# tracker_main.net
KiCad netlist of a schematic drawn in Altium Designer
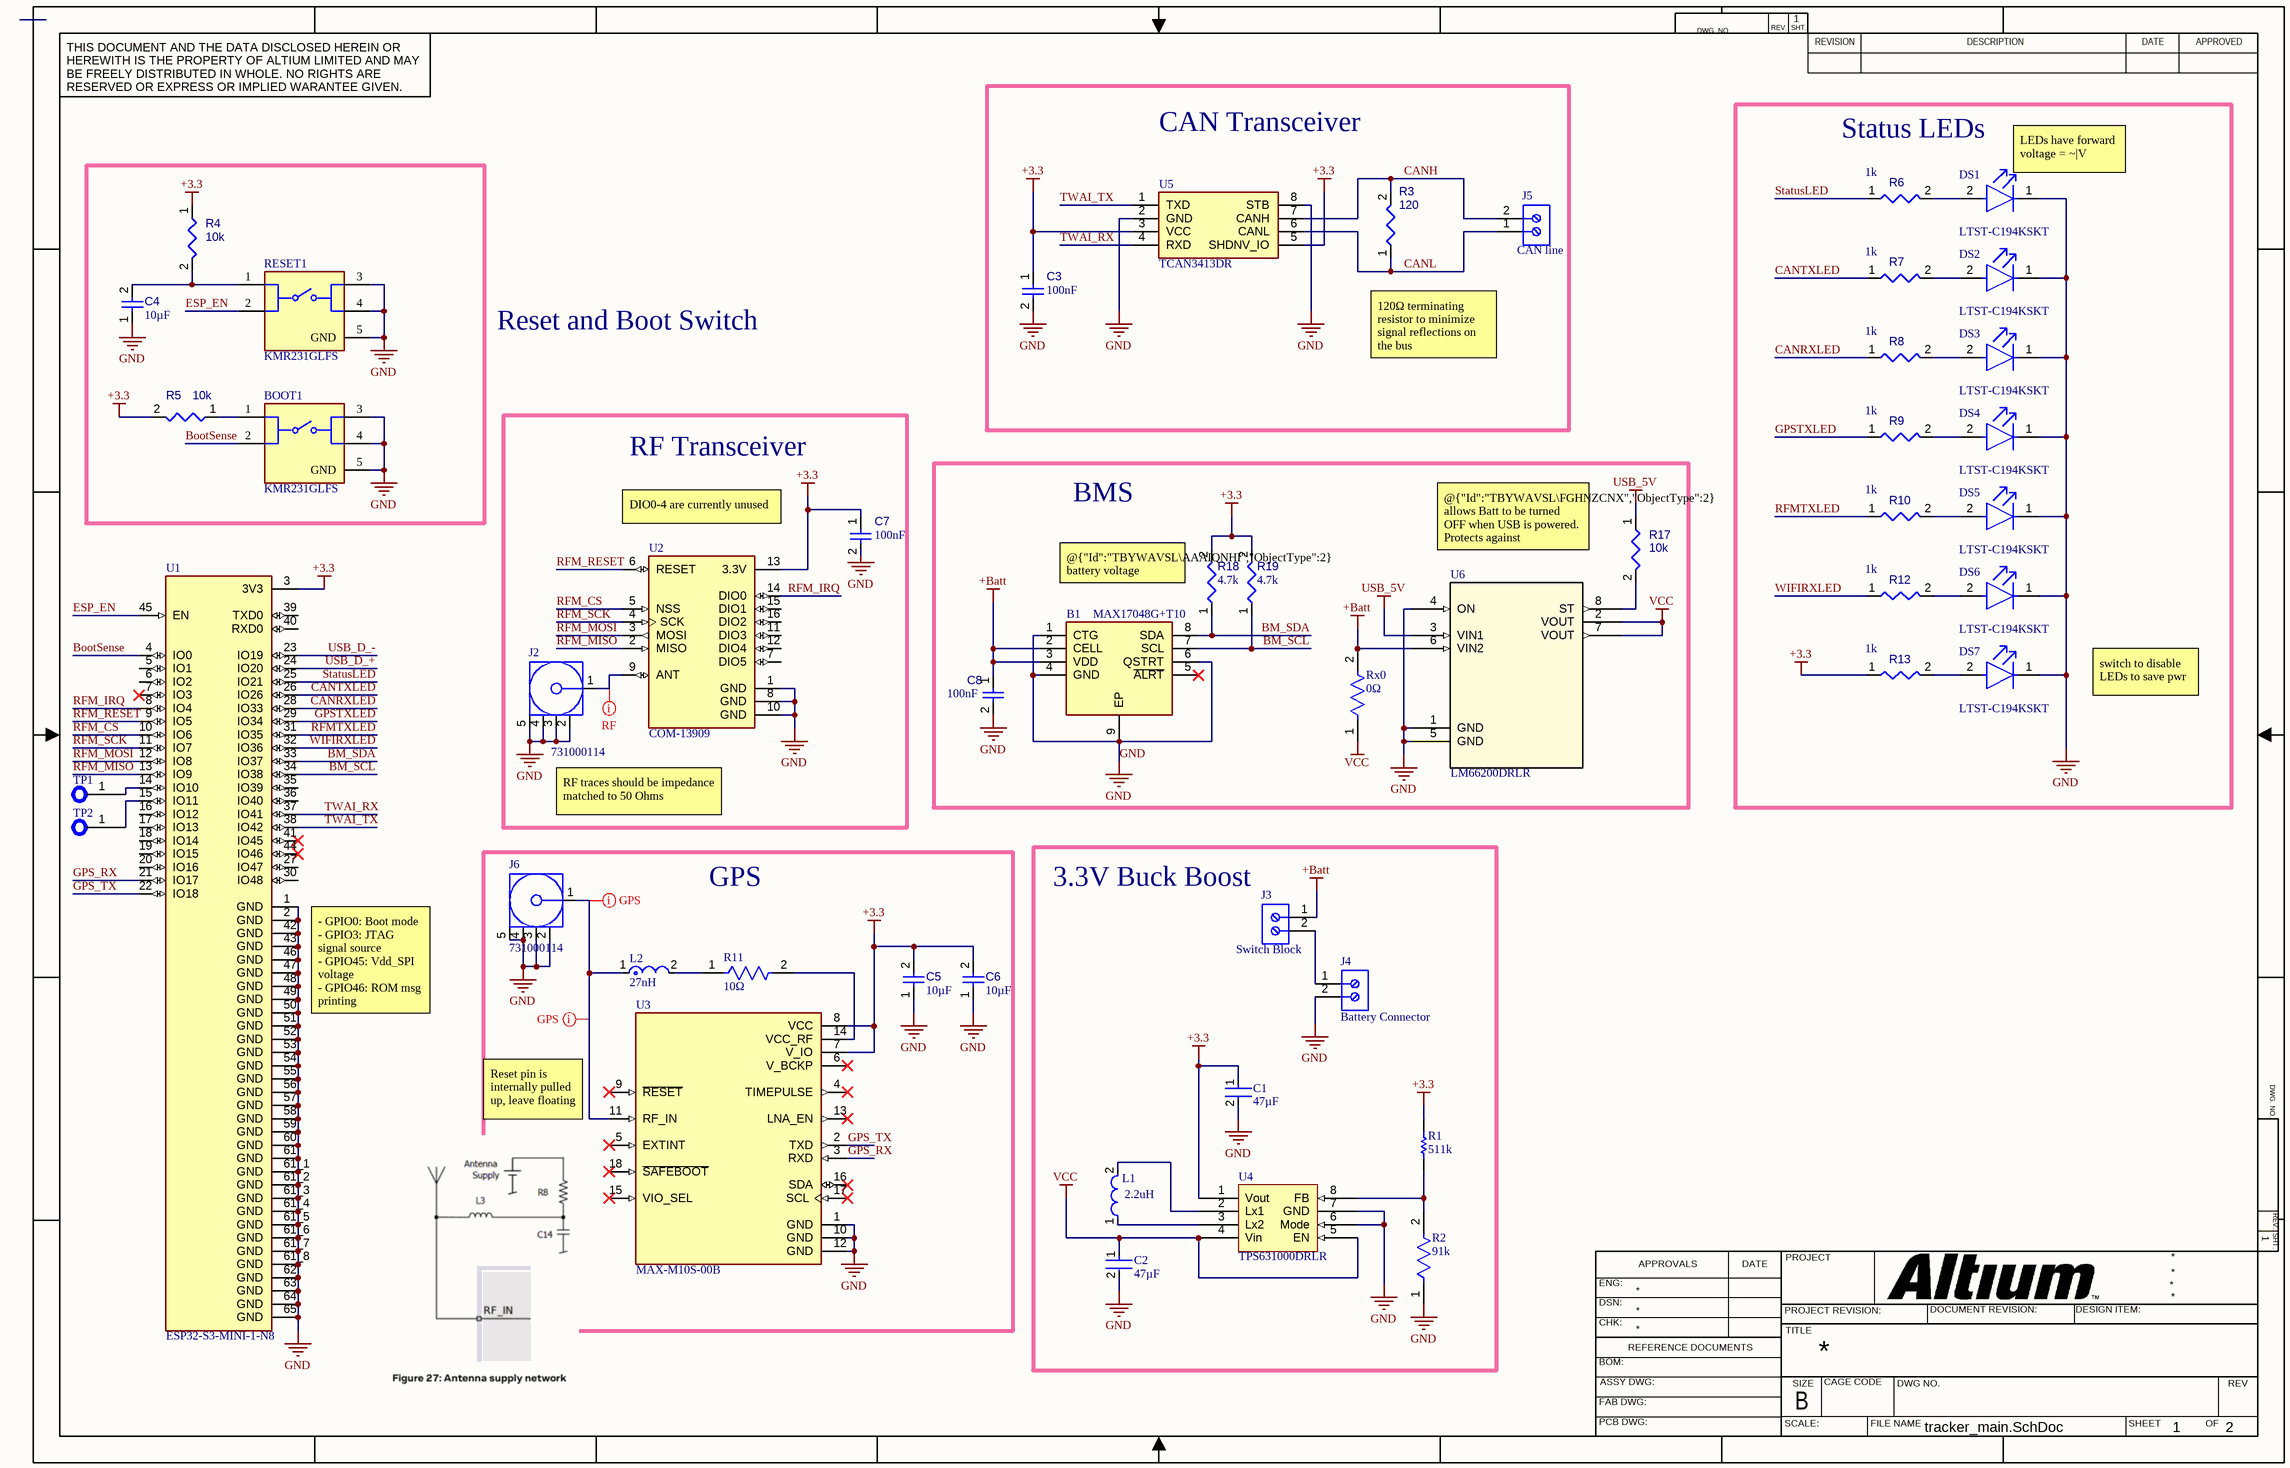
[diagram p0: tracker_main.SchDoc]

(export (version "E")
  (design (tool "Eeschema 10.0.6"))
  (components
    (comp (ref "B1")
      (value "MAX17048G+T10")
      (footprint "SON50P200X200X80-9N-D")
      (description "3A 1-Cell/2-Cell Fuel Gauge with ModelGauge")
      (fields (field (name "MOUSER PART NUMBER") "700-MAX17048G+T10"))
      (libsource (lib "UTD Workspace") (part "MAX17048G+T10"))
    )
    (comp (ref "BOOT1")
      (value "KMR231GLFS")
      (footprint "FP-KMR231GLFS-MFG")
      (description "SWITCH TACTILE SPST-NO 0.05A 32V")
      (libsource (lib "Altium Content Vault") (part "4ba73034ab40b7b0ce053ff7ec1e5b4"))
    )
    (comp (ref "C1")
      (value "47µF")
      (footprint "FP-0603-L_1_6_0_2-W_0_8_0-MFG")
      (description "CAP CER 47UF 6.3V X5R 0603\r\n06036D476MAT2A")
      (fields (field (name "TOLERANCE") "20%"))
      (libsource (lib "Altium Content Vault") (part "02cd4be3c70576c341d710602a673aa"))
    )
    (comp (ref "C2")
      (value "47µF")
      (footprint "FP-0603-L_1_6_0_2-W_0_8_0-MFG")
      (description "CAP CER 47UF 6.3V X5R 0603\r\n06036D476MAT2A")
      (fields (field (name "TOLERANCE") "20%"))
      (libsource (lib "Altium Content Vault") (part "02cd4be3c70576c341d710602a673aa"))
    )
    (comp (ref "C3")
      (value "100nF")
      (footprint "CAPC1608X90X40NL10T20")
      (description "Chip Capacitor, 100 nF, +/- 10%, 50 V, 0603 (1608 Metric)")
      (fields (field (name "TOLERANCE") "10%"))
      (libsource (lib "Aadesh Senthilkumar") (part "CAP-NP-2"))
    )
    (comp (ref "C4")
      (value "10µF")
      (footprint "CAPC0603(1608)100_L")
      (description "Chip Capacitor, 10µF +/-20%, 10V, 0603, Thickness 1 mm")
      (fields (field (name "TOLERANCE") "10%") (field (name "Comment") "Capacitor 10µF +/-20% 10V 0603"))
      (libsource (lib "The University of Texas at Dallas") (part "CAP-NP-2"))
    )
    (comp (ref "C5")
      (value "10µF")
      (footprint "CAPC0603(1608)100_L")
      (description "Chip Capacitor, 10µF +/-20%, 10V, 0603, Thickness 1 mm")
      (fields (field (name "TOLERANCE") "10%") (field (name "Comment") "Capacitor 10µF +/-20% 10V 0603"))
      (libsource (lib "The University of Texas at Dallas") (part "CAP-NP-2"))
    )
    (comp (ref "C6")
      (value "10µF")
      (footprint "CAPC0603(1608)100_L")
      (description "Chip Capacitor, 10µF +/-20%, 10V, 0603, Thickness 1 mm")
      (fields (field (name "TOLERANCE") "10%") (field (name "Comment") "Capacitor 10µF +/-20% 10V 0603"))
      (libsource (lib "The University of Texas at Dallas") (part "CAP-NP-2"))
    )
    (comp (ref "C7")
      (value "100nF")
      (footprint "CAPC1608X90X40NL10T20")
      (description "Chip Capacitor, 100 nF, +/- 10%, 50 V, 0603 (1608 Metric)")
      (fields (field (name "TOLERANCE") "10%"))
      (libsource (lib "Aadesh Senthilkumar") (part "CAP-NP-2"))
    )
    (comp (ref "C8")
      (value "100nF")
      (footprint "CAPC1608X90X40NL10T20")
      (description "Chip Capacitor, 100 nF, +/- 10%, 50 V, 0603 (1608 Metric)")
      (fields (field (name "TOLERANCE") "10%"))
      (libsource (lib "Aadesh Senthilkumar") (part "CAP-NP-2"))
    )
    (comp (ref "DS1")
      (value "LTST-C194KSKT")
      (footprint "FP-LTST-C194KSKT-MFG")
      (description "Single Color LED, Yellow, Water Clear, 1.15mm")
      (libsource (lib "UTD Workspace") (part "8706943c75ba83719d021d2fdc84c58"))
    )
    (comp (ref "DS2")
      (value "LTST-C194KSKT")
      (footprint "FP-LTST-C194KSKT-MFG")
      (description "Single Color LED, Yellow, Water Clear, 1.15mm")
      (libsource (lib "UTD Workspace") (part "8706943c75ba83719d021d2fdc84c58"))
    )
    (comp (ref "DS3")
      (value "LTST-C194KSKT")
      (footprint "FP-LTST-C194KSKT-MFG")
      (description "Single Color LED, Yellow, Water Clear, 1.15mm")
      (libsource (lib "UTD Workspace") (part "8706943c75ba83719d021d2fdc84c58"))
    )
    (comp (ref "DS4")
      (value "LTST-C194KSKT")
      (footprint "FP-LTST-C194KSKT-MFG")
      (description "Single Color LED, Yellow, Water Clear, 1.15mm")
      (libsource (lib "UTD Workspace") (part "8706943c75ba83719d021d2fdc84c58"))
    )
    (comp (ref "DS5")
      (value "LTST-C194KSKT")
      (footprint "FP-LTST-C194KSKT-MFG")
      (description "Single Color LED, Yellow, Water Clear, 1.15mm")
      (libsource (lib "UTD Workspace") (part "8706943c75ba83719d021d2fdc84c58"))
    )
    (comp (ref "DS6")
      (value "LTST-C194KSKT")
      (footprint "FP-LTST-C194KSKT-MFG")
      (description "Single Color LED, Yellow, Water Clear, 1.15mm")
      (libsource (lib "UTD Workspace") (part "8706943c75ba83719d021d2fdc84c58"))
    )
    (comp (ref "DS7")
      (value "LTST-C194KSKT")
      (footprint "FP-LTST-C194KSKT-MFG")
      (description "Single Color LED, Yellow, Water Clear, 1.15mm")
      (libsource (lib "UTD Workspace") (part "8706943c75ba83719d021d2fdc84c58"))
    )
    (comp (ref "J2")
      (value "731000114")
      (footprint "MOLX-731000114_V")
      (description "SMA Right-Angle PCB Jack Receptacle, Brass Body, Gold Plated, 50 Ohm, 5-Pin THD, RoHS, Tray")
      (fields (field (name "MANUFACTURER") "Molex"))
      (libsource (lib "Altium Content Vault") (part "CN-S-4F-RF5"))
    )
    (comp (ref "J3")
      (value "Switch Block")
      (footprint "PHOE-1725656-2")
      (description "Male Header, Pitch 2.54 mm, 1 x 2 Position, Height 9 mm, Tail Length 3.5 mm")
      (fields
        (field (name "MANUFACTURER PART NO.") "1725656")
        (field (name "MANUFACTURER") "Phoenix Contact")
      )
      (libsource (lib "Altium Content Vault") (part "CN-1P-F-TB2"))
    )
    (comp (ref "J4")
      (value "Battery Connector")
      (footprint "PHOE-1725656-2")
      (description "Male Header, Pitch 2.54 mm, 1 x 2 Position, Height 9 mm, Tail Length 3.5 mm")
      (fields
        (field (name "MANUFACTURER PART NO.") "1725656")
        (field (name "MANUFACTURER") "Phoenix Contact")
      )
      (libsource (lib "Altium Content Vault") (part "CN-1P-F-TB2"))
    )
    (comp (ref "J5")
      (value "CAN line")
      (footprint "PHOE-1725656-2")
      (description "Male Header, Pitch 2.54 mm, 1 x 2 Position, Height 9 mm, Tail Length 3.5 mm")
      (fields
        (field (name "MANUFACTURER PART NO.") "1725656")
        (field (name "MANUFACTURER") "Phoenix Contact")
      )
      (libsource (lib "Altium Content Vault") (part "CN-1P-F-TB2"))
    )
    (comp (ref "J6")
      (value "731000114")
      (footprint "MOLX-731000114_V")
      (description "SMA Right-Angle PCB Jack Receptacle, Brass Body, Gold Plated, 50 Ohm, 5-Pin THD, RoHS, Tray")
      (fields (field (name "MANUFACTURER") "Molex"))
      (libsource (lib "Altium Content Vault") (part "CN-S-4F-RF5"))
    )
    (comp (ref "L1")
      (value "2.2uH")
      (footprint "FP-DFE21CC_EL-MFG")
      (description "FIXED IND 2.2UH 2100MA NONAUTO")
      (fields (field (name "Comment") "DFE21CCN2R2MELL"))
      (libsource (lib "Altium Content Vault") (part "725321dda6339637d4d059423bc1c3c"))
    )
    (comp (ref "L2")
      (value "27nH")
      (footprint "FP-LQG18HH_00-IPC_C")
      (description "Multilayer type Inductor for Automotive 27nH ±5% 0.54Ω 500mA 0603 LQG18HH27NJ00D")
      (libsource (lib "Altium Content Vault") (part "4cc4b267dca4c8e51f7102f422741d8"))
    )
    (comp (ref "R1")
      (value "511k")
      (footprint "RESC1609X50X30NL10T20")
      (description "CRCW0603511KFKEA\r\nRes Thick Film 0603 511K Ohm 1% 0.1W(1/10W) ±100ppm/C Pad SMD Automotive T/R")
      (fields (field (name "PART NUMBER") "CRCW0603511KFKEA") (field (name "MANUFACTURER") "Vishay Dale"))
      (libsource (lib "Altium Content Vault") (part "RES"))
    )
    (comp (ref "R2")
      (value "91k")
      (footprint "FP-CRCW0603-HPe3-IPC_B")
      (description "CRCW060391K0FKEAHP\r\nRES Thick Film, 91kΩ, 1%, 0.33W, 100ppm/°C, 0603")
      (fields (field (name "TOLERANCE") "1%"))
      (libsource (lib "Altium Content Vault") (part "1029c3af85768c4190bb7ad29bc67b5"))
    )
    (comp (ref "R3")
      (value "120")
      (footprint "RESC0603(1608)_L")
      (description "Chip Resistor, 120 Ohms, +/-5 %, 0.1 W, -55 to 155 degC, 0603")
      (fields (field (name "TOLERANCE") "5%") (field (name "POWER") "100mW"))
      (libsource (lib "Aadesh Senthilkumar") (part "RES-2"))
    )
    (comp (ref "R4")
      (value "10k")
      (footprint "RESC1608X55X25ML10T15")
      (description "Chip Resistor, 10 KOhm, +/- 1%, 01 W, -55 to 155 degC, 0603 (1608 Metric)")
      (fields (field (name "POWER") "100mW") (field (name "TOLERANCE") "1%"))
      (libsource (lib "Aadesh Senthilkumar") (part "RES-2"))
    )
    (comp (ref "R5")
      (value "10k")
      (footprint "RESC1608X55X25ML10T15")
      (description "Chip Resistor, 10 KOhm, +/- 1%, 01 W, -55 to 155 degC, 0603 (1608 Metric)")
      (fields (field (name "POWER") "100mW") (field (name "TOLERANCE") "1%"))
      (libsource (lib "Aadesh Senthilkumar") (part "RES-2"))
    )
    (comp (ref "R6")
      (value "1k")
      (footprint "RESC1608X55X25ML10T15")
      (description "Chip Resistor, 1 KOhm, +/-1%, 0.1 W, -55 to 155 degC, 0603 (1608 Metric)")
      (fields (field (name "TOLERANCE") "1%") (field (name "POWER") "100mW"))
      (libsource (lib "UTD Workspace") (part "RES-2"))
    )
    (comp (ref "R7")
      (value "1k")
      (footprint "RESC1608X55X25ML10T15")
      (description "Chip Resistor, 1 KOhm, +/-1%, 0.1 W, -55 to 155 degC, 0603 (1608 Metric)")
      (fields (field (name "TOLERANCE") "1%") (field (name "POWER") "100mW"))
      (libsource (lib "UTD Workspace") (part "RES-2"))
    )
    (comp (ref "R8")
      (value "1k")
      (footprint "RESC1608X55X25ML10T15")
      (description "Chip Resistor, 1 KOhm, +/-1%, 0.1 W, -55 to 155 degC, 0603 (1608 Metric)")
      (fields (field (name "TOLERANCE") "1%") (field (name "POWER") "100mW"))
      (libsource (lib "UTD Workspace") (part "RES-2"))
    )
    (comp (ref "R9")
      (value "1k")
      (footprint "RESC1608X55X25ML10T15")
      (description "Chip Resistor, 1 KOhm, +/-1%, 0.1 W, -55 to 155 degC, 0603 (1608 Metric)")
      (fields (field (name "TOLERANCE") "1%") (field (name "POWER") "100mW"))
      (libsource (lib "UTD Workspace") (part "RES-2"))
    )
    (comp (ref "R10")
      (value "1k")
      (footprint "RESC1608X55X25ML10T15")
      (description "Chip Resistor, 1 KOhm, +/-1%, 0.1 W, -55 to 155 degC, 0603 (1608 Metric)")
      (fields (field (name "TOLERANCE") "1%") (field (name "POWER") "100mW"))
      (libsource (lib "UTD Workspace") (part "RES-2"))
    )
    (comp (ref "R11")
      (value "10Ω")
      (footprint "FP-RNCF0603-MFG")
      (description "RES 10 OHM 0.05% 1/10W 0603 RNCF0603AKT10R0")
      (fields (field (name "TOLERANCE") "0.05%"))
      (libsource (lib "Altium Content Vault") (part "1029c3af85768c4190bb7ad29bc67b5"))
    )
    (comp (ref "R12")
      (value "1k")
      (footprint "RESC1608X55X25ML10T15")
      (description "Chip Resistor, 1 KOhm, +/-1%, 0.1 W, -55 to 155 degC, 0603 (1608 Metric)")
      (fields (field (name "TOLERANCE") "1%") (field (name "POWER") "100mW"))
      (libsource (lib "UTD Workspace") (part "RES-2"))
    )
    (comp (ref "R13")
      (value "1k")
      (footprint "RESC1608X55X25ML10T15")
      (description "Chip Resistor, 1 KOhm, +/-1%, 0.1 W, -55 to 155 degC, 0603 (1608 Metric)")
      (fields (field (name "TOLERANCE") "1%") (field (name "POWER") "100mW"))
      (libsource (lib "UTD Workspace") (part "RES-2"))
    )
    (comp (ref "R17")
      (value "10k")
      (footprint "RESC1608X55X25ML10T15")
      (description "Chip Resistor, 10 KOhm, +/- 1%, 01 W, -55 to 155 degC, 0603 (1608 Metric)")
      (fields (field (name "POWER") "100mW") (field (name "TOLERANCE") "1%"))
      (libsource (lib "Aadesh Senthilkumar") (part "RES-2"))
    )
    (comp (ref "R18")
      (value "4.7k")
      (footprint "RESC1608X55X25ML10T15")
      (description "Chip Resistor, 4.7 KOhm, +/- 1%, 0.1 W, -55 to 155 degC, 0603 (1608 Metric)")
      (fields (field (name "TOLERANCE") "1%") (field (name "POWER") "100mW"))
      (libsource (lib "UTD Workspace") (part "RES-2"))
    )
    (comp (ref "R19")
      (value "4.7k")
      (footprint "RESC1608X55X25ML10T15")
      (description "Chip Resistor, 4.7 KOhm, +/- 1%, 0.1 W, -55 to 155 degC, 0603 (1608 Metric)")
      (fields (field (name "TOLERANCE") "1%") (field (name "POWER") "100mW"))
      (libsource (lib "UTD Workspace") (part "RES-2"))
    )
    (comp (ref "RESET1")
      (value "KMR231GLFS")
      (footprint "FP-KMR231GLFS-MFG")
      (description "SWITCH TACTILE SPST-NO 0.05A 32V")
      (libsource (lib "Altium Content Vault") (part "4ba73034ab40b7b0ce053ff7ec1e5b4"))
    )
    (comp (ref "Rx0")
      (value "0Ω")
      (footprint "FP-HCJ0805-MFG")
      (description "RES 0 OHM JUMPER 1/2W 0805")
      (libsource (lib "Altium Content Vault") (part "1029c3af85768c4190bb7ad29bc67b5"))
    )
    (comp (ref "TP1") (value "TP_1") (footprint "Testpoint1") (libsource (lib "Schlib1") (part "Testpoint1")))
    (comp (ref "TP2") (value "TP_1") (footprint "Testpoint1") (libsource (lib "Schlib1") (part "Testpoint1")))
    (comp (ref "U1")
      (value "ESP32-S3-MINI-1-N8")
      (footprint "XCVR_ESP32-S3-MINI-1-N8")
      (description "SMD module, ESP32-S3FN8, 8 MB SPI flash, PCB antenna")
      (fields (field (name "MF") "{'manufacturer': u'Espressif Systems'}"))
      (libsource (lib "Aadesh Senthilkumar") (part "ESP32-S3-MINI-1-N8"))
    )
    (comp (ref "U2")
      (value "COM-13909")
      (footprint "MOD_COM-13909")
      (description "Rfm69hcw Wireless Transceiver 91")
      (libsource (lib "UTD Workspace") (part "COM-13909"))
    )
    (comp (ref "U3")
      (value "MAX-M10S-00B")
      (footprint "XCVR_MAX-M10S-00B")
      (description "Gnss / Gps Modules U-Blox M10 Gnss Module Rom, Tcxo, Lna, Saw Lcc, 9.7X10 Mm, 500 Pcs/Reel")
      (libsource (lib "Aadesh Senthilkumar") (part "MAX-M10S-00B"))
    )
    (comp (ref "U4")
      (value "TPS631000DRLR")
      (footprint "SON50P120X60-8N")
      (description "1.5-A output current, high-power-density buck-boost converter 8-SOT-5X3 -40 to 125")
      (libsource (lib "The University of Texas at Dallas") (part "TPS631000DRLR-Symbol-1"))
    )
    (comp (ref "U5")
      (value "TCAN3413DR")
      (footprint "SamacSys:SOIC127P600X175-8N")
      (description "Integrated Circuit")
      (fields (field (name "MOUSER PART NUMBER") "595-TCAN3413DR"))
      (libsource (lib "*") (part "TCAN3413DR"))
    )
    (comp (ref "U6")
      (value "LM66200DRLR")
      (footprint "SOT-5X3_DRL_TEX")
      (description "1.6-V to 5.5-V, 40-mâ„")
      (fields (field (name "COPYRIGHT") "Copyright (C) 2025 Ultra Librarian. All rights reserved."))
      (libsource (lib "UTD Workspace") (part "LM66200DRLR"))
    )
  )
  (nets
    (net (code "1") (name "+3.3") (class "Default")
      (node (ref "C1") (pin "1") (pinfunction "1_1") (pintype "passive"))
      (node (ref "C3") (pin "1") (pinfunction "1_1") (pintype "passive"))
      (node (ref "C5") (pin "2") (pinfunction "2_2") (pintype "passive"))
      (node (ref "C6") (pin "2") (pinfunction "2_2") (pintype "passive"))
      (node (ref "C7") (pin "1") (pinfunction "1_1") (pintype "passive"))
      (node (ref "R1") (pin "2") (pinfunction "2_2") (pintype "passive"))
      (node (ref "R13") (pin "1") (pinfunction "1_1") (pintype "passive"))
      (node (ref "R18") (pin "2") (pinfunction "2_2") (pintype "passive"))
      (node (ref "R19") (pin "2") (pinfunction "2_2") (pintype "passive"))
      (node (ref "R4") (pin "1") (pinfunction "1_1") (pintype "passive"))
      (node (ref "R5") (pin "2") (pinfunction "2_2") (pintype "passive"))
      (node (ref "U1") (pin "3") (pinfunction "3V3_3") (pintype "power_in"))
      (node (ref "U2") (pin "13") (pinfunction "3.3V_13") (pintype "power_in"))
      (node (ref "U3") (pin "7") (pinfunction "V_IO_7") (pintype "power_in"))
      (node (ref "U3") (pin "8") (pinfunction "VCC_8") (pintype "power_in"))
      (node (ref "U4") (pin "1") (pinfunction "Vout_1") (pintype "power_in"))
      (node (ref "U5") (pin "3") (pinfunction "VCC_3") (pintype "passive"))
      (node (ref "U5") (pin "5") (pinfunction "SHDNV_IO_5") (pintype "passive"))
    )
    (net (code "2") (name "+Batt") (class "Default")
      (node (ref "B1") (pin "2") (pinfunction "CELL_2") (pintype "passive"))
      (node (ref "B1") (pin "3") (pinfunction "VDD_3") (pintype "passive"))
      (node (ref "C8") (pin "1") (pinfunction "1_1") (pintype "passive"))
      (node (ref "J3") (pin "1") (pinfunction "1_1") (pintype "passive"))
      (node (ref "Rx0") (pin "2") (pinfunction "2_2") (pintype "passive"))
      (node (ref "U6") (pin "6") (pinfunction "VIN2_6") (pintype "input"))
    )
    (net (code "3") (name "/BM_SCL") (class "Default")
      (node (ref "B1") (pin "7") (pinfunction "SCL_7") (pintype "passive"))
      (node (ref "R19") (pin "1") (pinfunction "1_1") (pintype "passive"))
      (node (ref "U1") (pin "34") (pinfunction "IO38_34") (pintype "bidirectional"))
    )
    (net (code "4") (name "/BM_SDA") (class "Default")
      (node (ref "B1") (pin "8") (pinfunction "SDA_8") (pintype "passive"))
      (node (ref "R18") (pin "1") (pinfunction "1_1") (pintype "passive"))
      (node (ref "U1") (pin "33") (pinfunction "IO37_33") (pintype "bidirectional"))
    )
    (net (code "5") (name "/BootSense") (class "Default")
      (node (ref "BOOT1") (pin "2") (pinfunction "2_2") (pintype "passive"))
      (node (ref "U1") (pin "4") (pinfunction "IO0_4") (pintype "bidirectional"))
    )
    (net (code "6") (name "/CANH") (class "Default")
      (node (ref "J5") (pin "2") (pinfunction "2_2") (pintype "passive"))
      (node (ref "R3") (pin "2") (pinfunction "2_2") (pintype "passive"))
      (node (ref "U5") (pin "7") (pinfunction "CANH_7") (pintype "passive"))
    )
    (net (code "7") (name "/CANL") (class "Default")
      (node (ref "J5") (pin "1") (pinfunction "1_1") (pintype "passive"))
      (node (ref "R3") (pin "1") (pinfunction "1_1") (pintype "passive"))
      (node (ref "U5") (pin "6") (pinfunction "CANL_6") (pintype "passive"))
    )
    (net (code "8") (name "/CANRXLED") (class "Default")
      (node (ref "R8") (pin "1") (pinfunction "1_1") (pintype "passive"))
      (node (ref "U1") (pin "28") (pinfunction "IO33_28") (pintype "bidirectional"))
    )
    (net (code "9") (name "/CANTXLED") (class "Default")
      (node (ref "R7") (pin "1") (pinfunction "1_1") (pintype "passive"))
      (node (ref "U1") (pin "26") (pinfunction "IO26_26") (pintype "bidirectional"))
    )
    (net (code "10") (name "/ESP_EN") (class "Default")
      (node (ref "RESET1") (pin "2") (pinfunction "2_2") (pintype "passive"))
      (node (ref "U1") (pin "45") (pinfunction "EN_45") (pintype "input"))
    )
    (net (code "11") (name "/GPSTXLED") (class "Default")
      (node (ref "R9") (pin "1") (pinfunction "1_1") (pintype "passive"))
      (node (ref "U1") (pin "29") (pinfunction "IO34_29") (pintype "bidirectional"))
    )
    (net (code "12") (name "/GPS_RX") (class "Default")
      (node (ref "U1") (pin "21") (pinfunction "IO17_21") (pintype "bidirectional"))
      (node (ref "U3") (pin "3") (pinfunction "RXD_3") (pintype "input"))
    )
    (net (code "13") (name "/GPS_TX") (class "Default")
      (node (ref "U1") (pin "22") (pinfunction "IO18_22") (pintype "bidirectional"))
      (node (ref "U3") (pin "2") (pinfunction "TXD_2") (pintype "output"))
    )
    (net (code "14") (name "/RFMTXLED") (class "Default")
      (node (ref "R10") (pin "1") (pinfunction "1_1") (pintype "passive"))
      (node (ref "U1") (pin "31") (pinfunction "IO35_31") (pintype "bidirectional"))
    )
    (net (code "15") (name "/RFM_CS") (class "Default")
      (node (ref "U1") (pin "10") (pinfunction "IO6_10") (pintype "bidirectional"))
      (node (ref "U2") (pin "5") (pinfunction "NSS_5") (pintype "input"))
    )
    (net (code "16") (name "/RFM_IRQ") (class "Default")
      (node (ref "U1") (pin "8") (pinfunction "IO4_8") (pintype "bidirectional"))
      (node (ref "U2") (pin "14") (pinfunction "DIO0_14") (pintype "bidirectional"))
    )
    (net (code "17") (name "/RFM_MISO") (class "Default")
      (node (ref "U1") (pin "13") (pinfunction "IO9_13") (pintype "bidirectional"))
      (node (ref "U2") (pin "2") (pinfunction "MISO_2") (pintype "input"))
    )
    (net (code "18") (name "/RFM_MOSI") (class "Default")
      (node (ref "U1") (pin "12") (pinfunction "IO8_12") (pintype "bidirectional"))
      (node (ref "U2") (pin "3") (pinfunction "MOSI_3") (pintype "output"))
    )
    (net (code "19") (name "/RFM_RESET") (class "Default")
      (node (ref "U1") (pin "9") (pinfunction "IO5_9") (pintype "bidirectional"))
      (node (ref "U2") (pin "6") (pinfunction "RESET_6") (pintype "bidirectional"))
    )
    (net (code "20") (name "/RFM_SCK") (class "Default")
      (node (ref "U1") (pin "11") (pinfunction "IO7_11") (pintype "bidirectional"))
      (node (ref "U2") (pin "4") (pinfunction "SCK_4") (pintype "input"))
    )
    (net (code "21") (name "/StatusLED") (class "Default")
      (node (ref "R6") (pin "1") (pinfunction "1_1") (pintype "passive"))
      (node (ref "U1") (pin "25") (pinfunction "IO21_25") (pintype "bidirectional"))
    )
    (net (code "22") (name "/TWAI_RX") (class "Default")
      (node (ref "U1") (pin "37") (pinfunction "IO41_37") (pintype "bidirectional"))
      (node (ref "U5") (pin "4") (pinfunction "RXD_4") (pintype "passive"))
    )
    (net (code "23") (name "/TWAI_TX") (class "Default")
      (node (ref "U1") (pin "38") (pinfunction "IO42_38") (pintype "bidirectional"))
      (node (ref "U5") (pin "1") (pinfunction "TXD_1") (pintype "passive"))
    )
    (net (code "24") (name "/USB_D_+") (class "Default")
      (node (ref "U1") (pin "24") (pinfunction "IO20_24") (pintype "bidirectional"))
    )
    (net (code "25") (name "/USB_D_-") (class "Default")
      (node (ref "U1") (pin "23") (pinfunction "IO19_23") (pintype "bidirectional"))
    )
    (net (code "26") (name "/WIFIRXLED") (class "Default")
      (node (ref "R12") (pin "1") (pinfunction "1_1") (pintype "passive"))
      (node (ref "U1") (pin "32") (pinfunction "IO36_32") (pintype "bidirectional"))
    )
    (net (code "27") (name "GND") (class "Default")
      (node (ref "B1") (pin "1") (pinfunction "CTG_1") (pintype "passive"))
      (node (ref "B1") (pin "4") (pinfunction "GND_4") (pintype "passive"))
      (node (ref "B1") (pin "6") (pinfunction "QSTRT_6") (pintype "passive"))
      (node (ref "B1") (pin "9") (pinfunction "EP_9") (pintype "passive"))
      (node (ref "BOOT1") (pin "3") (pinfunction "3_3") (pintype "passive"))
      (node (ref "BOOT1") (pin "4") (pinfunction "4_4") (pintype "passive"))
      (node (ref "BOOT1") (pin "5") (pinfunction "GND_5") (pintype "power_in"))
      (node (ref "C1") (pin "2") (pinfunction "2_2") (pintype "passive"))
      (node (ref "C2") (pin "2") (pinfunction "2_2") (pintype "passive"))
      (node (ref "C3") (pin "2") (pinfunction "2_2") (pintype "passive"))
      (node (ref "C4") (pin "1") (pinfunction "1_1") (pintype "passive"))
      (node (ref "C5") (pin "1") (pinfunction "1_1") (pintype "passive"))
      (node (ref "C6") (pin "1") (pinfunction "1_1") (pintype "passive"))
      (node (ref "C7") (pin "2") (pinfunction "2_2") (pintype "passive"))
      (node (ref "C8") (pin "2") (pinfunction "2_2") (pintype "passive"))
      (node (ref "DS1") (pin "1") (pinfunction "C_1") (pintype "passive"))
      (node (ref "DS2") (pin "1") (pinfunction "C_1") (pintype "passive"))
      (node (ref "DS3") (pin "1") (pinfunction "C_1") (pintype "passive"))
      (node (ref "DS4") (pin "1") (pinfunction "C_1") (pintype "passive"))
      (node (ref "DS5") (pin "1") (pinfunction "C_1") (pintype "passive"))
      (node (ref "DS6") (pin "1") (pinfunction "C_1") (pintype "passive"))
      (node (ref "DS7") (pin "1") (pinfunction "C_1") (pintype "passive"))
      (node (ref "J2") (pin "2") (pinfunction "2_2") (pintype "passive"))
      (node (ref "J2") (pin "3") (pinfunction "3_3") (pintype "passive"))
      (node (ref "J2") (pin "4") (pinfunction "4_4") (pintype "passive"))
      (node (ref "J2") (pin "5") (pinfunction "5_5") (pintype "passive"))
      (node (ref "J4") (pin "2") (pinfunction "2_2") (pintype "passive"))
      (node (ref "J6") (pin "2") (pinfunction "2_2") (pintype "passive"))
      (node (ref "J6") (pin "3") (pinfunction "3_3") (pintype "passive"))
      (node (ref "J6") (pin "4") (pinfunction "4_4") (pintype "passive"))
      (node (ref "J6") (pin "5") (pinfunction "5_5") (pintype "passive"))
      (node (ref "R2") (pin "1") (pinfunction "1_1") (pintype "passive"))
      (node (ref "RESET1") (pin "3") (pinfunction "3_3") (pintype "passive"))
      (node (ref "RESET1") (pin "4") (pinfunction "4_4") (pintype "passive"))
      (node (ref "RESET1") (pin "5") (pinfunction "GND_5") (pintype "power_in"))
      (node (ref "U1") (pin "1") (pinfunction "GND_1") (pintype "power_in"))
      (node (ref "U1") (pin "2") (pinfunction "GND_2") (pintype "power_in"))
      (node (ref "U1") (pin "42") (pinfunction "GND_42") (pintype "power_in"))
      (node (ref "U1") (pin "43") (pinfunction "GND_43") (pintype "power_in"))
      (node (ref "U1") (pin "46") (pinfunction "GND_46") (pintype "power_in"))
      (node (ref "U1") (pin "47") (pinfunction "GND_47") (pintype "power_in"))
      (node (ref "U1") (pin "48") (pinfunction "GND_48") (pintype "power_in"))
      (node (ref "U1") (pin "49") (pinfunction "GND_49") (pintype "power_in"))
      (node (ref "U1") (pin "50") (pinfunction "GND_50") (pintype "power_in"))
      (node (ref "U1") (pin "51") (pinfunction "GND_51") (pintype "power_in"))
      (node (ref "U1") (pin "52") (pinfunction "GND_52") (pintype "power_in"))
      (node (ref "U1") (pin "53") (pinfunction "GND_53") (pintype "power_in"))
      (node (ref "U1") (pin "54") (pinfunction "GND_54") (pintype "power_in"))
      (node (ref "U1") (pin "55") (pinfunction "GND_55") (pintype "power_in"))
      (node (ref "U1") (pin "56") (pinfunction "GND_56") (pintype "power_in"))
      (node (ref "U1") (pin "57") (pinfunction "GND_57") (pintype "power_in"))
      (node (ref "U1") (pin "58") (pinfunction "GND_58") (pintype "power_in"))
      (node (ref "U1") (pin "59") (pinfunction "GND_59") (pintype "power_in"))
      (node (ref "U1") (pin "60") (pinfunction "GND_60") (pintype "power_in"))
      (node (ref "U1") (pin "61") (pinfunction "GND_61") (pintype "power_in"))
      (node (ref "U1") (pin "61_1") (pinfunction "GND_61_1") (pintype "power_in"))
      (node (ref "U1") (pin "61_2") (pinfunction "GND_61_2") (pintype "power_in"))
      (node (ref "U1") (pin "61_3") (pinfunction "GND_61_3") (pintype "power_in"))
      (node (ref "U1") (pin "61_4") (pinfunction "GND_61_4") (pintype "power_in"))
      (node (ref "U1") (pin "61_5") (pinfunction "GND_61_5") (pintype "power_in"))
      (node (ref "U1") (pin "61_6") (pinfunction "GND_61_6") (pintype "power_in"))
      (node (ref "U1") (pin "61_7") (pinfunction "GND_61_7") (pintype "power_in"))
      (node (ref "U1") (pin "61_8") (pinfunction "GND_61_8") (pintype "power_in"))
      (node (ref "U1") (pin "62") (pinfunction "GND_62") (pintype "power_in"))
      (node (ref "U1") (pin "63") (pinfunction "GND_63") (pintype "power_in"))
      (node (ref "U1") (pin "64") (pinfunction "GND_64") (pintype "power_in"))
      (node (ref "U1") (pin "65") (pinfunction "GND_65") (pintype "power_in"))
      (node (ref "U2") (pin "1") (pinfunction "GND_1") (pintype "power_in"))
      (node (ref "U2") (pin "10") (pinfunction "GND_10") (pintype "power_in"))
      (node (ref "U2") (pin "8") (pinfunction "GND_8") (pintype "power_in"))
      (node (ref "U3") (pin "1") (pinfunction "GND_1") (pintype "power_in"))
      (node (ref "U3") (pin "10") (pinfunction "GND_10") (pintype "power_in"))
      (node (ref "U3") (pin "12") (pinfunction "GND_12") (pintype "power_in"))
      (node (ref "U4") (pin "6") (pinfunction "Mode_6") (pintype "input"))
      (node (ref "U4") (pin "7") (pinfunction "GND_7") (pintype "power_in"))
      (node (ref "U5") (pin "2") (pinfunction "GND_2") (pintype "passive"))
      (node (ref "U5") (pin "8") (pinfunction "STB_8") (pintype "passive"))
      (node (ref "U6") (pin "1") (pinfunction "GND_1") (pintype "power_in"))
      (node (ref "U6") (pin "4") (pinfunction "ON_4") (pintype "input"))
      (node (ref "U6") (pin "5") (pinfunction "GND_5") (pintype "power_in"))
    )
    (net (code "28") (name "Net-(BOOT1-Pad1)") (class "Default")
      (node (ref "BOOT1") (pin "1") (pinfunction "1_1") (pintype "passive"))
      (node (ref "R5") (pin "1") (pinfunction "1_1") (pintype "passive"))
    )
    (net (code "29") (name "Net-(C4-Pad2)") (class "Default")
      (node (ref "C4") (pin "2") (pinfunction "2_2") (pintype "passive"))
      (node (ref "R4") (pin "2") (pinfunction "2_2") (pintype "passive"))
      (node (ref "RESET1") (pin "1") (pinfunction "1_1") (pintype "passive"))
    )
    (net (code "30") (name "Net-(DS1-A)") (class "Default")
      (node (ref "DS1") (pin "2") (pinfunction "A_2") (pintype "passive"))
      (node (ref "R6") (pin "2") (pinfunction "2_2") (pintype "passive"))
    )
    (net (code "31") (name "Net-(DS2-A)") (class "Default")
      (node (ref "DS2") (pin "2") (pinfunction "A_2") (pintype "passive"))
      (node (ref "R7") (pin "2") (pinfunction "2_2") (pintype "passive"))
    )
    (net (code "32") (name "Net-(DS3-A)") (class "Default")
      (node (ref "DS3") (pin "2") (pinfunction "A_2") (pintype "passive"))
      (node (ref "R8") (pin "2") (pinfunction "2_2") (pintype "passive"))
    )
    (net (code "33") (name "Net-(DS4-A)") (class "Default")
      (node (ref "DS4") (pin "2") (pinfunction "A_2") (pintype "passive"))
      (node (ref "R9") (pin "2") (pinfunction "2_2") (pintype "passive"))
    )
    (net (code "34") (name "Net-(DS5-A)") (class "Default")
      (node (ref "DS5") (pin "2") (pinfunction "A_2") (pintype "passive"))
      (node (ref "R10") (pin "2") (pinfunction "2_2") (pintype "passive"))
    )
    (net (code "35") (name "Net-(DS6-A)") (class "Default")
      (node (ref "DS6") (pin "2") (pinfunction "A_2") (pintype "passive"))
      (node (ref "R12") (pin "2") (pinfunction "2_2") (pintype "passive"))
    )
    (net (code "36") (name "Net-(DS7-A)") (class "Default")
      (node (ref "DS7") (pin "2") (pinfunction "A_2") (pintype "passive"))
      (node (ref "R13") (pin "2") (pinfunction "2_2") (pintype "passive"))
    )
    (net (code "37") (name "Net-(J3-Pad2)") (class "Default")
      (node (ref "J3") (pin "2") (pinfunction "2_2") (pintype "passive"))
      (node (ref "J4") (pin "1") (pinfunction "1_1") (pintype "passive"))
    )
    (net (code "38") (name "Net-(L2-Pad2)") (class "Default")
      (node (ref "L2") (pin "2") (pinfunction "2_2") (pintype "passive"))
      (node (ref "R11") (pin "1") (pinfunction "1_1") (pintype "passive"))
    )
    (net (code "39") (name "Net-(U1-IO10)") (class "Default")
      (node (ref "TP1") (pin "1") (pinfunction "1_1") (pintype "passive"))
      (node (ref "U1") (pin "14") (pinfunction "IO10_14") (pintype "bidirectional"))
    )
    (net (code "40") (name "Net-(U1-IO11)") (class "Default")
      (node (ref "TP2") (pin "1") (pinfunction "1_1") (pintype "passive"))
      (node (ref "U1") (pin "15") (pinfunction "IO11_15") (pintype "bidirectional"))
    )
    (net (code "41") (name "Net-(U2-ANT)") (class "Default")
      (node (ref "J2") (pin "1") (pinfunction "1_1") (pintype "passive"))
      (node (ref "U2") (pin "9") (pinfunction "ANT_9") (pintype "bidirectional"))
    )
    (net (code "42") (name "Net-(U3-RF_IN)") (class "Default")
      (node (ref "J6") (pin "1") (pinfunction "1_1") (pintype "passive"))
      (node (ref "L2") (pin "1") (pinfunction "1_1") (pintype "passive"))
      (node (ref "U3") (pin "11") (pinfunction "RF_IN_11") (pintype "input"))
    )
    (net (code "43") (name "Net-(U3-VCC_RF)") (class "Default")
      (node (ref "R11") (pin "2") (pinfunction "2_2") (pintype "passive"))
      (node (ref "U3") (pin "14") (pinfunction "VCC_RF_14") (pintype "power_in"))
    )
    (net (code "44") (name "Net-(U4-FB)") (class "Default")
      (node (ref "R1") (pin "1") (pinfunction "1_1") (pintype "passive"))
      (node (ref "R2") (pin "2") (pinfunction "2_2") (pintype "passive"))
      (node (ref "U4") (pin "8") (pinfunction "FB_8") (pintype "input"))
    )
    (net (code "45") (name "Net-(U4-Lx1)") (class "Default")
      (node (ref "L1") (pin "2") (pinfunction "2_2") (pintype "passive"))
      (node (ref "U4") (pin "2") (pinfunction "Lx1_2") (pintype "power_in"))
    )
    (net (code "46") (name "Net-(U4-Lx2)") (class "Default")
      (node (ref "L1") (pin "1") (pinfunction "1_1") (pintype "passive"))
      (node (ref "U4") (pin "3") (pinfunction "Lx2_3") (pintype "power_in"))
    )
    (net (code "47") (name "Net-(U6-ST)") (class "Default")
      (node (ref "R17") (pin "2") (pinfunction "2_2") (pintype "passive"))
      (node (ref "U6") (pin "8") (pinfunction "ST_8") (pintype "output"))
    )
    (net (code "48") (name "USB_5V") (class "Default")
      (node (ref "R17") (pin "1") (pinfunction "1_1") (pintype "passive"))
      (node (ref "U6") (pin "3") (pinfunction "VIN1_3") (pintype "input"))
    )
    (net (code "49") (name "VCC") (class "Default")
      (node (ref "C2") (pin "1") (pinfunction "1_1") (pintype "passive"))
      (node (ref "Rx0") (pin "1") (pinfunction "1_1") (pintype "passive"))
      (node (ref "U4") (pin "4") (pinfunction "Vin_4") (pintype "power_in"))
      (node (ref "U4") (pin "5") (pinfunction "EN_5") (pintype "input"))
      (node (ref "U6") (pin "2") (pinfunction "VOUT_2") (pintype "power_in"))
      (node (ref "U6") (pin "7") (pinfunction "VOUT_7") (pintype "output"))
    )
    (net (code "50") (name "unconnected-(B1-~{ALRT}-Pad5)") (class "Default")
      (node (ref "B1") (pin "5") (pinfunction "~{ALRT}_5") (pintype "passive+no_connect"))
    )
    (net (code "51") (name "unconnected-(U1-IO1-Pad5)") (class "Default")
      (node (ref "U1") (pin "5") (pinfunction "IO1_5") (pintype "bidirectional"))
    )
    (net (code "52") (name "unconnected-(U1-IO2-Pad6)") (class "Default")
      (node (ref "U1") (pin "6") (pinfunction "IO2_6") (pintype "bidirectional"))
    )
    (net (code "53") (name "unconnected-(U1-IO3-Pad7)") (class "Default")
      (node (ref "U1") (pin "7") (pinfunction "IO3_7") (pintype "bidirectional+no_connect"))
    )
    (net (code "54") (name "unconnected-(U1-IO12-Pad16)") (class "Default")
      (node (ref "U1") (pin "16") (pinfunction "IO12_16") (pintype "bidirectional"))
    )
    (net (code "55") (name "unconnected-(U1-IO13-Pad17)") (class "Default")
      (node (ref "U1") (pin "17") (pinfunction "IO13_17") (pintype "bidirectional"))
    )
    (net (code "56") (name "unconnected-(U1-IO14-Pad18)") (class "Default")
      (node (ref "U1") (pin "18") (pinfunction "IO14_18") (pintype "bidirectional"))
    )
    (net (code "57") (name "unconnected-(U1-IO15-Pad19)") (class "Default")
      (node (ref "U1") (pin "19") (pinfunction "IO15_19") (pintype "bidirectional"))
    )
    (net (code "58") (name "unconnected-(U1-IO16-Pad20)") (class "Default")
      (node (ref "U1") (pin "20") (pinfunction "IO16_20") (pintype "bidirectional"))
    )
    (net (code "59") (name "unconnected-(U1-IO39-Pad35)") (class "Default")
      (node (ref "U1") (pin "35") (pinfunction "IO39_35") (pintype "bidirectional"))
    )
    (net (code "60") (name "unconnected-(U1-IO40-Pad36)") (class "Default")
      (node (ref "U1") (pin "36") (pinfunction "IO40_36") (pintype "bidirectional"))
    )
    (net (code "61") (name "unconnected-(U1-IO45-Pad41)") (class "Default")
      (node (ref "U1") (pin "41") (pinfunction "IO45_41") (pintype "bidirectional+no_connect"))
    )
    (net (code "62") (name "unconnected-(U1-IO46-Pad44)") (class "Default")
      (node (ref "U1") (pin "44") (pinfunction "IO46_44") (pintype "bidirectional+no_connect"))
    )
    (net (code "63") (name "unconnected-(U1-IO47-Pad27)") (class "Default")
      (node (ref "U1") (pin "27") (pinfunction "IO47_27") (pintype "bidirectional"))
    )
    (net (code "64") (name "unconnected-(U1-IO48-Pad30)") (class "Default")
      (node (ref "U1") (pin "30") (pinfunction "IO48_30") (pintype "bidirectional"))
    )
    (net (code "65") (name "unconnected-(U1-RXD0-Pad40)") (class "Default")
      (node (ref "U1") (pin "40") (pinfunction "RXD0_40") (pintype "bidirectional"))
    )
    (net (code "66") (name "unconnected-(U1-TXD0-Pad39)") (class "Default")
      (node (ref "U1") (pin "39") (pinfunction "TXD0_39") (pintype "bidirectional"))
    )
    (net (code "67") (name "unconnected-(U2-DIO1-Pad15)") (class "Default")
      (node (ref "U2") (pin "15") (pinfunction "DIO1_15") (pintype "bidirectional"))
    )
    (net (code "68") (name "unconnected-(U2-DIO2-Pad16)") (class "Default")
      (node (ref "U2") (pin "16") (pinfunction "DIO2_16") (pintype "bidirectional"))
    )
    (net (code "69") (name "unconnected-(U2-DIO3-Pad11)") (class "Default")
      (node (ref "U2") (pin "11") (pinfunction "DIO3_11") (pintype "bidirectional"))
    )
    (net (code "70") (name "unconnected-(U2-DIO4-Pad12)") (class "Default")
      (node (ref "U2") (pin "12") (pinfunction "DIO4_12") (pintype "bidirectional"))
    )
    (net (code "71") (name "unconnected-(U2-DIO5-Pad7)") (class "Default")
      (node (ref "U2") (pin "7") (pinfunction "DIO5_7") (pintype "bidirectional"))
    )
    (net (code "72") (name "unconnected-(U3-EXTINT-Pad5)") (class "Default")
      (node (ref "U3") (pin "5") (pinfunction "EXTINT_5") (pintype "input+no_connect"))
    )
    (net (code "73") (name "unconnected-(U3-LNA_EN-Pad13)") (class "Default")
      (node (ref "U3") (pin "13") (pinfunction "LNA_EN_13") (pintype "output+no_connect"))
    )
    (net (code "74") (name "unconnected-(U3-SCL-Pad17)") (class "Default")
      (node (ref "U3") (pin "17") (pinfunction "SCL_17") (pintype "input+no_connect"))
    )
    (net (code "75") (name "unconnected-(U3-SDA-Pad16)") (class "Default")
      (node (ref "U3") (pin "16") (pinfunction "SDA_16") (pintype "bidirectional+no_connect"))
    )
    (net (code "76") (name "unconnected-(U3-TIMEPULSE-Pad4)") (class "Default")
      (node (ref "U3") (pin "4") (pinfunction "TIMEPULSE_4") (pintype "output+no_connect"))
    )
    (net (code "77") (name "unconnected-(U3-VIO_SEL-Pad15)") (class "Default")
      (node (ref "U3") (pin "15") (pinfunction "VIO_SEL_15") (pintype "input+no_connect"))
    )
    (net (code "78") (name "unconnected-(U3-V_BCKP-Pad6)") (class "Default")
      (node (ref "U3") (pin "6") (pinfunction "V_BCKP_6") (pintype "power_in+no_connect"))
    )
    (net (code "79") (name "unconnected-(U3-~{RESET}-Pad9)") (class "Default")
      (node (ref "U3") (pin "9") (pinfunction "~{RESET}_9") (pintype "input+no_connect"))
    )
    (net (code "80") (name "unconnected-(U3-~{SAFEBOOT}-Pad18)") (class "Default")
      (node (ref "U3") (pin "18") (pinfunction "~{SAFEBOOT}_18") (pintype "input+no_connect"))
    )
  )
)
